# MCU.net
KiCad netlist of a schematic drawn in Altium Designer
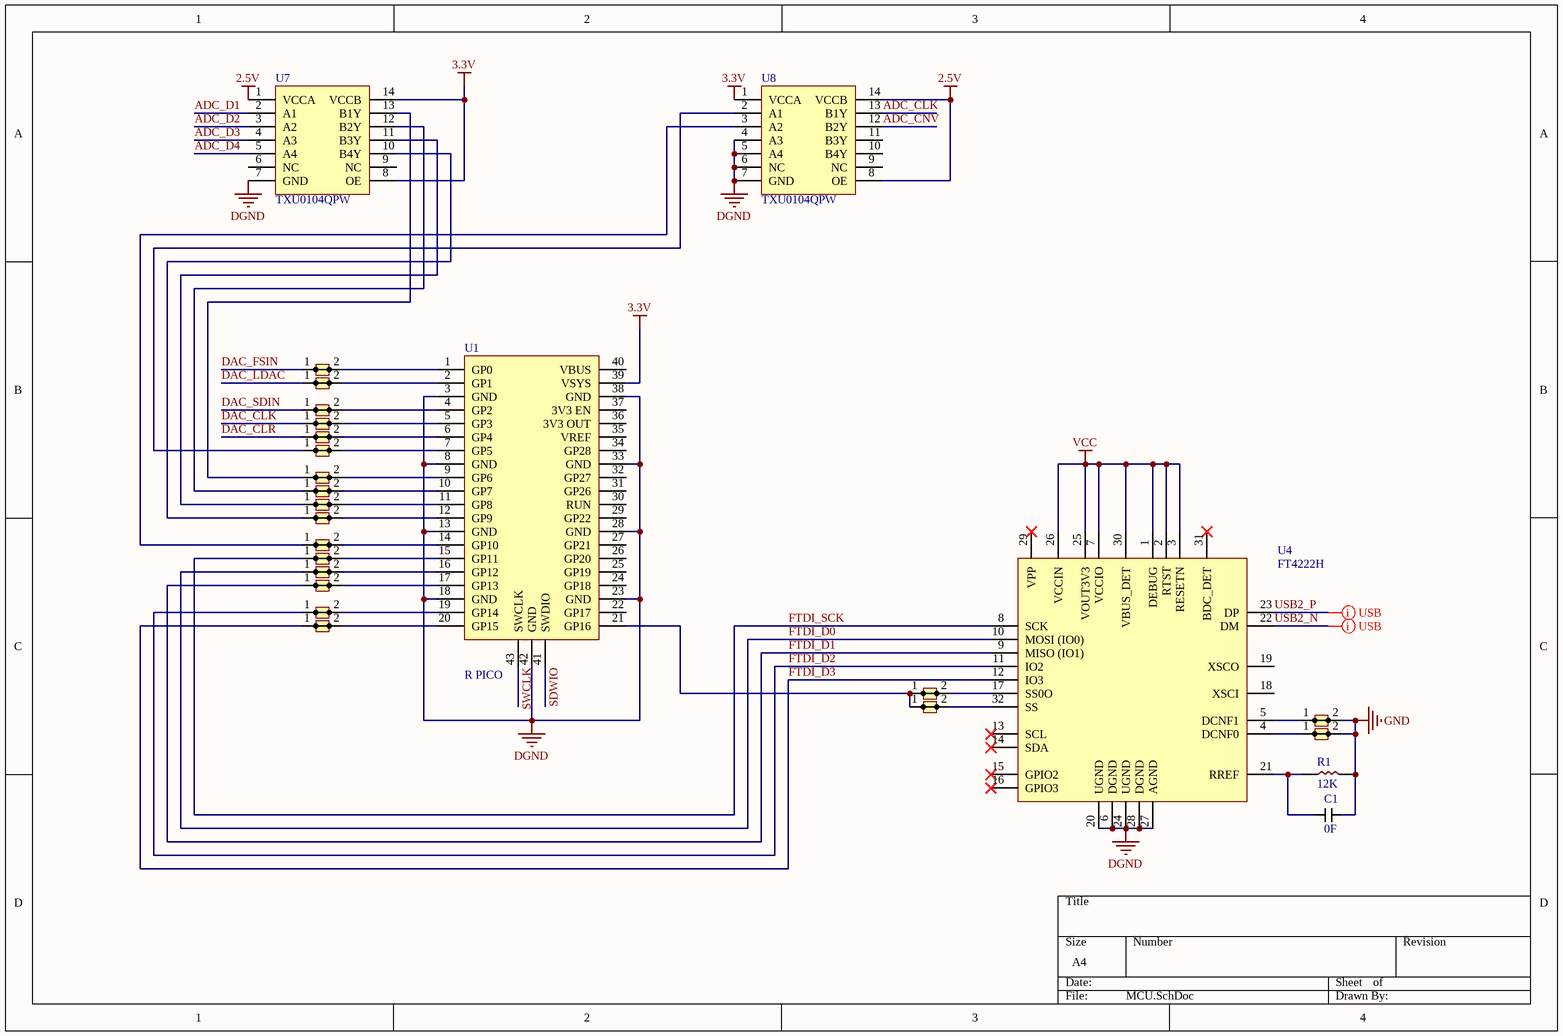
[diagram p0: MCU.SchDoc]

(export (version "E")
  (design (tool "Eeschema 10.0.6"))
  (components
    (comp (ref "C1") (value "0F") (footprint "C0805") (libsource (lib "SMU") (part "C0805")))
    (comp (ref "R1") (value "12K") (footprint "R0805") (libsource (lib "SMU") (part "R0805")))
    (comp (ref "SB1")
      (value "SolderBridge")
      (footprint "SB")
      (libsource (lib "OpenSEM") (part "SolderBridge"))
    )
    (comp (ref "SB2")
      (value "SolderBridge")
      (footprint "SB")
      (libsource (lib "OpenSEM") (part "SolderBridge"))
    )
    (comp (ref "SB3")
      (value "SolderBridge")
      (footprint "SB")
      (libsource (lib "OpenSEM") (part "SolderBridge"))
    )
    (comp (ref "SB4")
      (value "SolderBridge")
      (footprint "SB")
      (libsource (lib "OpenSEM") (part "SolderBridge"))
    )
    (comp (ref "SB5")
      (value "SolderBridge")
      (footprint "SB")
      (libsource (lib "OpenSEM") (part "SolderBridge"))
    )
    (comp (ref "SB6")
      (value "SolderBridge")
      (footprint "SB")
      (libsource (lib "OpenSEM") (part "SolderBridge"))
    )
    (comp (ref "SB7")
      (value "SolderBridge")
      (footprint "SB")
      (libsource (lib "OpenSEM") (part "SolderBridge"))
    )
    (comp (ref "SB8")
      (value "SolderBridge")
      (footprint "SB")
      (libsource (lib "OpenSEM") (part "SolderBridge"))
    )
    (comp (ref "SB9")
      (value "SolderBridge")
      (footprint "SB")
      (libsource (lib "OpenSEM") (part "SolderBridge"))
    )
    (comp (ref "SB10")
      (value "SolderBridge")
      (footprint "SB")
      (libsource (lib "OpenSEM") (part "SolderBridge"))
    )
    (comp (ref "SB11")
      (value "SolderBridge")
      (footprint "SB")
      (libsource (lib "OpenSEM") (part "SolderBridge"))
    )
    (comp (ref "SB12")
      (value "SolderBridge")
      (footprint "SB")
      (libsource (lib "OpenSEM") (part "SolderBridge"))
    )
    (comp (ref "SB13")
      (value "SolderBridge")
      (footprint "SB")
      (libsource (lib "OpenSEM") (part "SolderBridge"))
    )
    (comp (ref "SB14")
      (value "SolderBridge")
      (footprint "SB")
      (libsource (lib "OpenSEM") (part "SolderBridge"))
    )
    (comp (ref "SB15")
      (value "SolderBridge")
      (footprint "SB")
      (libsource (lib "OpenSEM") (part "SolderBridge"))
    )
    (comp (ref "SB16")
      (value "SolderBridge")
      (footprint "SB")
      (libsource (lib "OpenSEM") (part "SolderBridge"))
    )
    (comp (ref "SB17")
      (value "SolderBridge")
      (footprint "SB")
      (libsource (lib "OpenSEM") (part "SolderBridge"))
    )
    (comp (ref "SB18")
      (value "SolderBridge")
      (footprint "SB")
      (libsource (lib "OpenSEM") (part "SolderBridge"))
    )
    (comp (ref "SB19")
      (value "SolderBridge")
      (footprint "SB")
      (libsource (lib "OpenSEM") (part "SolderBridge"))
    )
    (comp (ref "SB20")
      (value "SolderBridge")
      (footprint "SB")
      (libsource (lib "OpenSEM") (part "SolderBridge"))
    )
    (comp (ref "U1") (value "R PICO") (footprint "RPICO") (libsource (lib "OpenSEM") (part "RaspPico")))
    (comp (ref "U4")
      (value "FT4222H")
      (footprint "QFN-32")
      (description "USB2.0 to QuadSPI/I2C\r\nBridge IC")
      (libsource (lib "OpenSEM") (part "FT4222H"))
    )
    (comp (ref "U7")
      (value "TXU0104QPW")
      (footprint "TSOP-14")
      (libsource (lib "OpenSEM") (part "TXU0104QPW"))
    )
    (comp (ref "U8")
      (value "TXU0104QPW")
      (footprint "TSOP-14")
      (libsource (lib "OpenSEM") (part "TXU0104QPW"))
    )
  )
  (nets
    (net (code "1") (name "/ADC_CLK") (class "Default")
      (node (ref "U8") (pin "13") (pinfunction "B1Y_13") (pintype "passive"))
    )
    (net (code "2") (name "/ADC_CNV") (class "Default")
      (node (ref "U8") (pin "12") (pinfunction "B2Y_12") (pintype "passive"))
    )
    (net (code "3") (name "/ADC_D1") (class "Default")
      (node (ref "U7") (pin "2") (pinfunction "A1_2") (pintype "passive"))
    )
    (net (code "4") (name "/ADC_D2") (class "Default")
      (node (ref "U7") (pin "3") (pinfunction "A2_3") (pintype "passive"))
    )
    (net (code "5") (name "/ADC_D3") (class "Default")
      (node (ref "U7") (pin "4") (pinfunction "A3_4") (pintype "passive"))
    )
    (net (code "6") (name "/ADC_D4") (class "Default")
      (node (ref "U7") (pin "5") (pinfunction "A4_5") (pintype "passive"))
    )
    (net (code "7") (name "/DAC_CLK") (class "Default") (node (ref "SB4") (pin "1") (pintype "passive")))
    (net (code "8") (name "/DAC_CLR") (class "Default") (node (ref "SB5") (pin "1") (pintype "passive")))
    (net (code "9") (name "/DAC_FSIN") (class "Default") (node (ref "SB1") (pin "1") (pintype "passive")))
    (net (code "10") (name "/DAC_LDAC") (class "Default") (node (ref "SB2") (pin "1") (pintype "passive")))
    (net (code "11") (name "/DAC_SDIN") (class "Default") (node (ref "SB3") (pin "1") (pintype "passive")))
    (net (code "12") (name "/FTDI_D0") (class "Default")
      (node (ref "SB13") (pin "1") (pintype "passive"))
      (node (ref "U4") (pin "10") (pinfunction "MOSI_(IO0)_10") (pintype "passive"))
    )
    (net (code "13") (name "/FTDI_D1") (class "Default")
      (node (ref "SB14") (pin "1") (pintype "passive"))
      (node (ref "U4") (pin "9") (pinfunction "MISO_(IO1)_9") (pintype "passive"))
    )
    (net (code "14") (name "/FTDI_D2") (class "Default")
      (node (ref "SB15") (pin "1") (pintype "passive"))
      (node (ref "U4") (pin "11") (pinfunction "IO2_11") (pintype "passive"))
    )
    (net (code "15") (name "/FTDI_D3") (class "Default")
      (node (ref "SB16") (pin "1") (pintype "passive"))
      (node (ref "U4") (pin "12") (pinfunction "IO3_12") (pintype "passive"))
    )
    (net (code "16") (name "/FTDI_SCK") (class "Default")
      (node (ref "SB12") (pin "1") (pintype "passive"))
      (node (ref "U4") (pin "8") (pinfunction "SCK_8") (pintype "passive"))
    )
    (net (code "17") (name "/SDWIO") (class "Default")
      (node (ref "U1") (pin "41") (pinfunction "SWDIO_41") (pintype "passive"))
    )
    (net (code "18") (name "/SWCLK") (class "Default")
      (node (ref "U1") (pin "43") (pinfunction "SWCLK_43") (pintype "passive"))
    )
    (net (code "19") (name "/USB2_N") (class "Default")
      (node (ref "U4") (pin "22") (pinfunction "DM_22") (pintype "passive"))
    )
    (net (code "20") (name "/USB2_P") (class "Default")
      (node (ref "U4") (pin "23") (pinfunction "DP_23") (pintype "passive"))
    )
    (net (code "21") (name "2.5V") (class "Default")
      (node (ref "U7") (pin "1") (pinfunction "VCCA_1") (pintype "passive"))
      (node (ref "U8") (pin "14") (pinfunction "VCCB_14") (pintype "passive"))
      (node (ref "U8") (pin "8") (pinfunction "OE_8") (pintype "passive"))
    )
    (net (code "22") (name "3.3V") (class "Default")
      (node (ref "U1") (pin "39") (pinfunction "VSYS_39") (pintype "passive"))
      (node (ref "U7") (pin "14") (pinfunction "VCCB_14") (pintype "passive"))
      (node (ref "U7") (pin "8") (pinfunction "OE_8") (pintype "passive"))
      (node (ref "U8") (pin "1") (pinfunction "VCCA_1") (pintype "passive"))
    )
    (net (code "23") (name "DGND") (class "Default")
      (node (ref "U1") (pin "13") (pinfunction "GND_13") (pintype "passive"))
      (node (ref "U1") (pin "18") (pinfunction "GND_18") (pintype "passive"))
      (node (ref "U1") (pin "23") (pinfunction "GND_23") (pintype "passive"))
      (node (ref "U1") (pin "28") (pinfunction "GND_28") (pintype "passive"))
      (node (ref "U1") (pin "3") (pinfunction "GND_3") (pintype "passive"))
      (node (ref "U1") (pin "33") (pinfunction "GND_33") (pintype "passive"))
      (node (ref "U1") (pin "38") (pinfunction "GND_38") (pintype "passive"))
      (node (ref "U1") (pin "42") (pinfunction "GND_42") (pintype "passive"))
      (node (ref "U1") (pin "8") (pinfunction "GND_8") (pintype "passive"))
      (node (ref "U4") (pin "20") (pinfunction "UGND_20") (pintype "passive"))
      (node (ref "U4") (pin "24") (pinfunction "UGND_24") (pintype "passive"))
      (node (ref "U4") (pin "27") (pinfunction "AGND_27") (pintype "passive"))
      (node (ref "U4") (pin "28") (pinfunction "DGND_28") (pintype "passive"))
      (node (ref "U4") (pin "6") (pinfunction "DGND_6") (pintype "passive"))
      (node (ref "U7") (pin "7") (pinfunction "GND_7") (pintype "passive"))
      (node (ref "U8") (pin "4") (pinfunction "A3_4") (pintype "passive"))
      (node (ref "U8") (pin "5") (pinfunction "A4_5") (pintype "passive"))
      (node (ref "U8") (pin "6") (pinfunction "NC_6") (pintype "passive"))
      (node (ref "U8") (pin "7") (pinfunction "GND_7") (pintype "passive"))
    )
    (net (code "24") (name "GND") (class "Default")
      (node (ref "C1") (pin "2") (pintype "passive"))
      (node (ref "R1") (pin "2") (pintype "passive"))
      (node (ref "SB19") (pin "2") (pintype "passive"))
      (node (ref "SB20") (pin "2") (pintype "passive"))
    )
    (net (code "25") (name "Net-(U1-GP0)") (class "Default")
      (node (ref "SB1") (pin "2") (pintype "passive"))
      (node (ref "U1") (pin "1") (pinfunction "GP0_1") (pintype "passive"))
    )
    (net (code "26") (name "Net-(U1-GP1)") (class "Default")
      (node (ref "SB2") (pin "2") (pintype "passive"))
      (node (ref "U1") (pin "2") (pinfunction "GP1_2") (pintype "passive"))
    )
    (net (code "27") (name "Net-(U1-GP2)") (class "Default")
      (node (ref "SB3") (pin "2") (pintype "passive"))
      (node (ref "U1") (pin "4") (pinfunction "GP2_4") (pintype "passive"))
    )
    (net (code "28") (name "Net-(U1-GP3)") (class "Default")
      (node (ref "SB4") (pin "2") (pintype "passive"))
      (node (ref "U1") (pin "5") (pinfunction "GP3_5") (pintype "passive"))
    )
    (net (code "29") (name "Net-(U1-GP4)") (class "Default")
      (node (ref "SB5") (pin "2") (pintype "passive"))
      (node (ref "U1") (pin "6") (pinfunction "GP4_6") (pintype "passive"))
    )
    (net (code "30") (name "Net-(U1-GP5)") (class "Default")
      (node (ref "SB6") (pin "2") (pintype "passive"))
      (node (ref "U1") (pin "7") (pinfunction "GP5_7") (pintype "passive"))
    )
    (net (code "31") (name "Net-(U1-GP6)") (class "Default")
      (node (ref "SB7") (pin "2") (pintype "passive"))
      (node (ref "U1") (pin "9") (pinfunction "GP6_9") (pintype "passive"))
    )
    (net (code "32") (name "Net-(U1-GP7)") (class "Default")
      (node (ref "SB8") (pin "2") (pintype "passive"))
      (node (ref "U1") (pin "10") (pinfunction "GP7_10") (pintype "passive"))
    )
    (net (code "33") (name "Net-(U1-GP8)") (class "Default")
      (node (ref "SB9") (pin "2") (pintype "passive"))
      (node (ref "U1") (pin "11") (pinfunction "GP8_11") (pintype "passive"))
    )
    (net (code "34") (name "Net-(U1-GP9)") (class "Default")
      (node (ref "SB10") (pin "2") (pintype "passive"))
      (node (ref "U1") (pin "12") (pinfunction "GP9_12") (pintype "passive"))
    )
    (net (code "35") (name "Net-(U1-GP10)") (class "Default")
      (node (ref "SB11") (pin "2") (pintype "passive"))
      (node (ref "U1") (pin "14") (pinfunction "GP10_14") (pintype "passive"))
    )
    (net (code "36") (name "Net-(U1-GP11)") (class "Default")
      (node (ref "SB12") (pin "2") (pintype "passive"))
      (node (ref "U1") (pin "15") (pinfunction "GP11_15") (pintype "passive"))
    )
    (net (code "37") (name "Net-(U1-GP12)") (class "Default")
      (node (ref "SB13") (pin "2") (pintype "passive"))
      (node (ref "U1") (pin "16") (pinfunction "GP12_16") (pintype "passive"))
    )
    (net (code "38") (name "Net-(U1-GP13)") (class "Default")
      (node (ref "SB14") (pin "2") (pintype "passive"))
      (node (ref "U1") (pin "17") (pinfunction "GP13_17") (pintype "passive"))
    )
    (net (code "39") (name "Net-(U1-GP14)") (class "Default")
      (node (ref "SB15") (pin "2") (pintype "passive"))
      (node (ref "U1") (pin "19") (pinfunction "GP14_19") (pintype "passive"))
    )
    (net (code "40") (name "Net-(U1-GP15)") (class "Default")
      (node (ref "SB16") (pin "2") (pintype "passive"))
      (node (ref "U1") (pin "20") (pinfunction "GP15_20") (pintype "passive"))
    )
    (net (code "41") (name "Net-(U1-GP16)") (class "Default")
      (node (ref "SB17") (pin "1") (pintype "passive"))
      (node (ref "SB18") (pin "1") (pintype "passive"))
      (node (ref "U1") (pin "21") (pinfunction "GP16_21") (pintype "passive"))
    )
    (net (code "42") (name "Net-(U4-DCNF0)") (class "Default")
      (node (ref "SB20") (pin "1") (pintype "passive"))
      (node (ref "U4") (pin "4") (pinfunction "DCNF0_4") (pintype "passive"))
    )
    (net (code "43") (name "Net-(U4-DCNF1)") (class "Default")
      (node (ref "SB19") (pin "1") (pintype "passive"))
      (node (ref "U4") (pin "5") (pinfunction "DCNF1_5") (pintype "passive"))
    )
    (net (code "44") (name "Net-(U4-RREF)") (class "Default")
      (node (ref "C1") (pin "1") (pintype "passive"))
      (node (ref "R1") (pin "1") (pintype "passive"))
      (node (ref "U4") (pin "21") (pinfunction "RREF_21") (pintype "passive"))
    )
    (net (code "45") (name "Net-(U4-SS)") (class "Default")
      (node (ref "SB18") (pin "2") (pintype "passive"))
      (node (ref "U4") (pin "32") (pinfunction "SS_32") (pintype "passive"))
    )
    (net (code "46") (name "Net-(U4-SS0O)") (class "Default")
      (node (ref "SB17") (pin "2") (pintype "passive"))
      (node (ref "U4") (pin "17") (pinfunction "SS0O_17") (pintype "passive"))
    )
    (net (code "47") (name "Net-(U7-B1Y)") (class "Default")
      (node (ref "SB7") (pin "1") (pintype "passive"))
      (node (ref "U7") (pin "13") (pinfunction "B1Y_13") (pintype "passive"))
    )
    (net (code "48") (name "Net-(U7-B2Y)") (class "Default")
      (node (ref "SB8") (pin "1") (pintype "passive"))
      (node (ref "U7") (pin "12") (pinfunction "B2Y_12") (pintype "passive"))
    )
    (net (code "49") (name "Net-(U7-B3Y)") (class "Default")
      (node (ref "SB9") (pin "1") (pintype "passive"))
      (node (ref "U7") (pin "11") (pinfunction "B3Y_11") (pintype "passive"))
    )
    (net (code "50") (name "Net-(U7-B4Y)") (class "Default")
      (node (ref "SB10") (pin "1") (pintype "passive"))
      (node (ref "U7") (pin "10") (pinfunction "B4Y_10") (pintype "passive"))
    )
    (net (code "51") (name "Net-(U8-A1)") (class "Default")
      (node (ref "SB6") (pin "1") (pintype "passive"))
      (node (ref "U8") (pin "2") (pinfunction "A1_2") (pintype "passive"))
    )
    (net (code "52") (name "Net-(U8-A2)") (class "Default")
      (node (ref "SB11") (pin "1") (pintype "passive"))
      (node (ref "U8") (pin "3") (pinfunction "A2_3") (pintype "passive"))
    )
    (net (code "53") (name "VCC") (class "Default")
      (node (ref "U4") (pin "1") (pinfunction "DEBUG_1") (pintype "passive"))
      (node (ref "U4") (pin "2") (pinfunction "RTST_2") (pintype "passive"))
      (node (ref "U4") (pin "25") (pinfunction "VOUT3V3_25") (pintype "passive"))
      (node (ref "U4") (pin "26") (pinfunction "VCCIN_26") (pintype "passive"))
      (node (ref "U4") (pin "3") (pinfunction "RESETN_3") (pintype "passive"))
      (node (ref "U4") (pin "30") (pinfunction "VBUS_DET_30") (pintype "passive"))
      (node (ref "U4") (pin "7") (pinfunction "VCCIO_7") (pintype "passive"))
    )
    (net (code "54") (name "unconnected-(U1-3V3_EN-Pad37)") (class "Default")
      (node (ref "U1") (pin "37") (pinfunction "3V3_EN_37") (pintype "passive"))
    )
    (net (code "55") (name "unconnected-(U1-3V3_OUT-Pad36)") (class "Default")
      (node (ref "U1") (pin "36") (pinfunction "3V3_OUT_36") (pintype "passive"))
    )
    (net (code "56") (name "unconnected-(U1-GP17-Pad22)") (class "Default")
      (node (ref "U1") (pin "22") (pinfunction "GP17_22") (pintype "passive"))
    )
    (net (code "57") (name "unconnected-(U1-GP18-Pad24)") (class "Default")
      (node (ref "U1") (pin "24") (pinfunction "GP18_24") (pintype "passive"))
    )
    (net (code "58") (name "unconnected-(U1-GP19-Pad25)") (class "Default")
      (node (ref "U1") (pin "25") (pinfunction "GP19_25") (pintype "passive"))
    )
    (net (code "59") (name "unconnected-(U1-GP20-Pad26)") (class "Default")
      (node (ref "U1") (pin "26") (pinfunction "GP20_26") (pintype "passive"))
    )
    (net (code "60") (name "unconnected-(U1-GP21-Pad27)") (class "Default")
      (node (ref "U1") (pin "27") (pinfunction "GP21_27") (pintype "passive"))
    )
    (net (code "61") (name "unconnected-(U1-GP22-Pad29)") (class "Default")
      (node (ref "U1") (pin "29") (pinfunction "GP22_29") (pintype "passive"))
    )
    (net (code "62") (name "unconnected-(U1-GP26-Pad31)") (class "Default")
      (node (ref "U1") (pin "31") (pinfunction "GP26_31") (pintype "passive"))
    )
    (net (code "63") (name "unconnected-(U1-GP27-Pad32)") (class "Default")
      (node (ref "U1") (pin "32") (pinfunction "GP27_32") (pintype "passive"))
    )
    (net (code "64") (name "unconnected-(U1-GP28-Pad34)") (class "Default")
      (node (ref "U1") (pin "34") (pinfunction "GP28_34") (pintype "passive"))
    )
    (net (code "65") (name "unconnected-(U1-RUN-Pad30)") (class "Default")
      (node (ref "U1") (pin "30") (pinfunction "RUN_30") (pintype "passive"))
    )
    (net (code "66") (name "unconnected-(U1-VBUS-Pad40)") (class "Default")
      (node (ref "U1") (pin "40") (pinfunction "VBUS_40") (pintype "passive"))
    )
    (net (code "67") (name "unconnected-(U1-VREF-Pad35)") (class "Default")
      (node (ref "U1") (pin "35") (pinfunction "VREF_35") (pintype "passive"))
    )
    (net (code "68") (name "unconnected-(U4-BDC_DET-Pad31)") (class "Default")
      (node (ref "U4") (pin "31") (pinfunction "BDC_DET_31") (pintype "passive+no_connect"))
    )
    (net (code "69") (name "unconnected-(U4-GPIO2-Pad15)") (class "Default")
      (node (ref "U4") (pin "15") (pinfunction "GPIO2_15") (pintype "passive+no_connect"))
    )
    (net (code "70") (name "unconnected-(U4-GPIO3-Pad16)") (class "Default")
      (node (ref "U4") (pin "16") (pinfunction "GPIO3_16") (pintype "passive+no_connect"))
    )
    (net (code "71") (name "unconnected-(U4-SCL-Pad13)") (class "Default")
      (node (ref "U4") (pin "13") (pinfunction "SCL_13") (pintype "passive+no_connect"))
    )
    (net (code "72") (name "unconnected-(U4-SDA-Pad14)") (class "Default")
      (node (ref "U4") (pin "14") (pinfunction "SDA_14") (pintype "passive+no_connect"))
    )
    (net (code "73") (name "unconnected-(U4-VPP-Pad29)") (class "Default")
      (node (ref "U4") (pin "29") (pinfunction "VPP_29") (pintype "passive+no_connect"))
    )
    (net (code "74") (name "unconnected-(U4-XSCI-Pad18)") (class "Default")
      (node (ref "U4") (pin "18") (pinfunction "XSCI_18") (pintype "passive"))
    )
    (net (code "75") (name "unconnected-(U4-XSCO-Pad19)") (class "Default")
      (node (ref "U4") (pin "19") (pinfunction "XSCO_19") (pintype "passive"))
    )
    (net (code "76") (name "unconnected-(U7-NC-Pad6)") (class "Default")
      (node (ref "U7") (pin "6") (pinfunction "NC_6") (pintype "passive"))
    )
    (net (code "77") (name "unconnected-(U7-NC-Pad9)") (class "Default")
      (node (ref "U7") (pin "9") (pinfunction "NC_9") (pintype "passive"))
    )
    (net (code "78") (name "unconnected-(U8-B3Y-Pad11)") (class "Default")
      (node (ref "U8") (pin "11") (pinfunction "B3Y_11") (pintype "passive"))
    )
    (net (code "79") (name "unconnected-(U8-B4Y-Pad10)") (class "Default")
      (node (ref "U8") (pin "10") (pinfunction "B4Y_10") (pintype "passive"))
    )
    (net (code "80") (name "unconnected-(U8-NC-Pad9)") (class "Default")
      (node (ref "U8") (pin "9") (pinfunction "NC_9") (pintype "passive"))
    )
  )
)
